# DC_bias_circuit.net
KiCad netlist of a schematic drawn in EAGLE
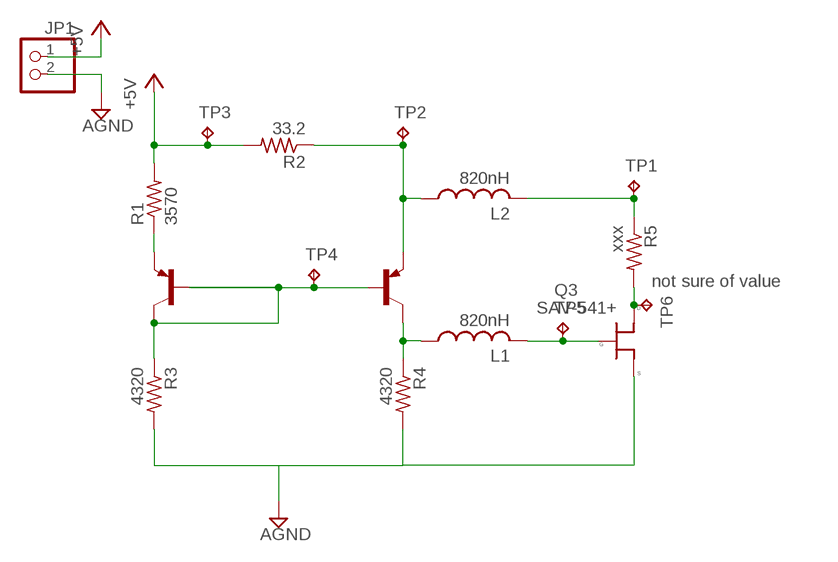
[diagram p0: schematic, sheet 1]

(export (version "E")
  (design (tool "Eeschema 10.0.6"))
  (components
    (comp (ref "JP1")
      (value "PINHD-1X2")
      (footprint "eagle-import:1X02")
      (libsource (lib "eagle-import") (part "PINHD-1X2"))
    )
    (comp (ref "L1")
      (value "820nH")
      (footprint "eagle-import:L3225M")
      (libsource (lib "eagle-import") (part "L-USL3225M"))
    )
    (comp (ref "L2")
      (value "820nH")
      (footprint "eagle-import:L3225M")
      (libsource (lib "eagle-import") (part "L-USL3225M"))
    )
    (comp (ref "Q1")
      (value "MMBT3906LT1SMD")
      (footprint "eagle-import:SOT23-BEC")
      (libsource (lib "eagle-import") (part "MMBT3906SMDLT1"))
    )
    (comp (ref "Q2")
      (value "MMBT3906LT1SMD")
      (footprint "eagle-import:SOT23-BEC")
      (libsource (lib "eagle-import") (part "MMBT3906SMDLT1"))
    )
    (comp (ref "Q3")
      (value "SAV-541+")
      (footprint "eagle-import:SOT-343")
      (libsource (lib "eagle-import") (part "SAV-541+"))
    )
    (comp (ref "R1")
      (value "3570")
      (footprint "eagle-import:M1206")
      (libsource (lib "eagle-import") (part "R-US_M1206"))
    )
    (comp (ref "R2")
      (value "33.2")
      (footprint "eagle-import:M1206")
      (libsource (lib "eagle-import") (part "R-US_M1206"))
    )
    (comp (ref "R3")
      (value "4320")
      (footprint "eagle-import:M1206")
      (libsource (lib "eagle-import") (part "R-US_M1206"))
    )
    (comp (ref "R4")
      (value "4320")
      (footprint "eagle-import:M1206")
      (libsource (lib "eagle-import") (part "R-US_M1206"))
    )
    (comp (ref "R5")
      (value "xxx")
      (footprint "eagle-import:M1206")
      (libsource (lib "eagle-import") (part "R-US_M1206"))
    )
    (comp (ref "TP1")
      (value "TPB1,27")
      (footprint "eagle-import:B1,27")
      (libsource (lib "eagle-import") (part "TPB1,27"))
    )
    (comp (ref "TP2")
      (value "TPB1,27")
      (footprint "eagle-import:B1,27")
      (libsource (lib "eagle-import") (part "TPB1,27"))
    )
    (comp (ref "TP3")
      (value "TPB1,27")
      (footprint "eagle-import:B1,27")
      (libsource (lib "eagle-import") (part "TPB1,27"))
    )
    (comp (ref "TP4")
      (value "TPB1,27")
      (footprint "eagle-import:B1,27")
      (libsource (lib "eagle-import") (part "TPB1,27"))
    )
    (comp (ref "TP5")
      (value "TPB1,27")
      (footprint "eagle-import:B1,27")
      (libsource (lib "eagle-import") (part "TPB1,27"))
    )
    (comp (ref "TP6")
      (value "TPB1,27")
      (footprint "eagle-import:B1,27")
      (libsource (lib "eagle-import") (part "TPB1,27"))
    )
  )
  (nets
    (net (code "1") (name "+5V") (class "Default")
      (node (ref "JP1") (pin "1") (pinfunction "1_1") (pintype "passive"))
      (node (ref "R1") (pin "2") (pinfunction "2_2") (pintype "passive"))
      (node (ref "R2") (pin "2") (pinfunction "2_2") (pintype "passive"))
      (node (ref "TP3") (pin "TP") (pinfunction "TP_TP") (pintype "input"))
    )
    (net (code "2") (name "AGND") (class "Default")
      (node (ref "JP1") (pin "2") (pinfunction "2_2") (pintype "passive"))
      (node (ref "Q3") (pin "2") (pinfunction "S_2") (pintype "passive"))
      (node (ref "Q3") (pin "4") (pinfunction "S_4") (pintype "passive"))
      (node (ref "R3") (pin "2") (pinfunction "2_2") (pintype "passive"))
      (node (ref "R4") (pin "2") (pinfunction "2_2") (pintype "passive"))
    )
    (net (code "3") (name "Net-(L1-Pad1)") (class "Default")
      (node (ref "L1") (pin "1") (pinfunction "1_1") (pintype "passive"))
      (node (ref "Q2") (pin "C") (pinfunction "C_C") (pintype "passive"))
      (node (ref "R4") (pin "1") (pinfunction "1_1") (pintype "passive"))
    )
    (net (code "4") (name "Net-(L2-Pad1)") (class "Default")
      (node (ref "L2") (pin "1") (pinfunction "1_1") (pintype "passive"))
      (node (ref "Q2") (pin "E") (pinfunction "E_E") (pintype "passive"))
      (node (ref "R2") (pin "1") (pinfunction "1_1") (pintype "passive"))
      (node (ref "TP2") (pin "TP") (pinfunction "TP_TP") (pintype "input"))
    )
    (net (code "5") (name "Net-(L2-Pad2)") (class "Default")
      (node (ref "L2") (pin "2") (pinfunction "2_2") (pintype "passive"))
      (node (ref "R5") (pin "1") (pinfunction "1_1") (pintype "passive"))
      (node (ref "TP1") (pin "TP") (pinfunction "TP_TP") (pintype "input"))
    )
    (net (code "6") (name "Net-(Q1-PadB)") (class "Default")
      (node (ref "Q1") (pin "B") (pinfunction "B_B") (pintype "passive"))
      (node (ref "Q1") (pin "C") (pinfunction "C_C") (pintype "passive"))
      (node (ref "Q2") (pin "B") (pinfunction "B_B") (pintype "passive"))
      (node (ref "R3") (pin "1") (pinfunction "1_1") (pintype "passive"))
      (node (ref "TP4") (pin "TP") (pinfunction "TP_TP") (pintype "input"))
    )
    (net (code "7") (name "Net-(Q1-PadE)") (class "Default")
      (node (ref "Q1") (pin "E") (pinfunction "E_E") (pintype "passive"))
      (node (ref "R1") (pin "1") (pinfunction "1_1") (pintype "passive"))
    )
    (net (code "8") (name "Net-(Q3-D)") (class "Default")
      (node (ref "Q3") (pin "1") (pinfunction "D_1") (pintype "passive"))
      (node (ref "R5") (pin "2") (pinfunction "2_2") (pintype "passive"))
      (node (ref "TP6") (pin "TP") (pinfunction "TP_TP") (pintype "input"))
    )
    (net (code "9") (name "Net-(Q3-G)") (class "Default")
      (node (ref "L1") (pin "2") (pinfunction "2_2") (pintype "passive"))
      (node (ref "Q3") (pin "3") (pinfunction "G_3") (pintype "passive"))
      (node (ref "TP5") (pin "TP") (pinfunction "TP_TP") (pintype "input"))
    )
  )
)
